# f_-_HomeAutomation.net
KiCad netlist of a schematic drawn in EAGLE
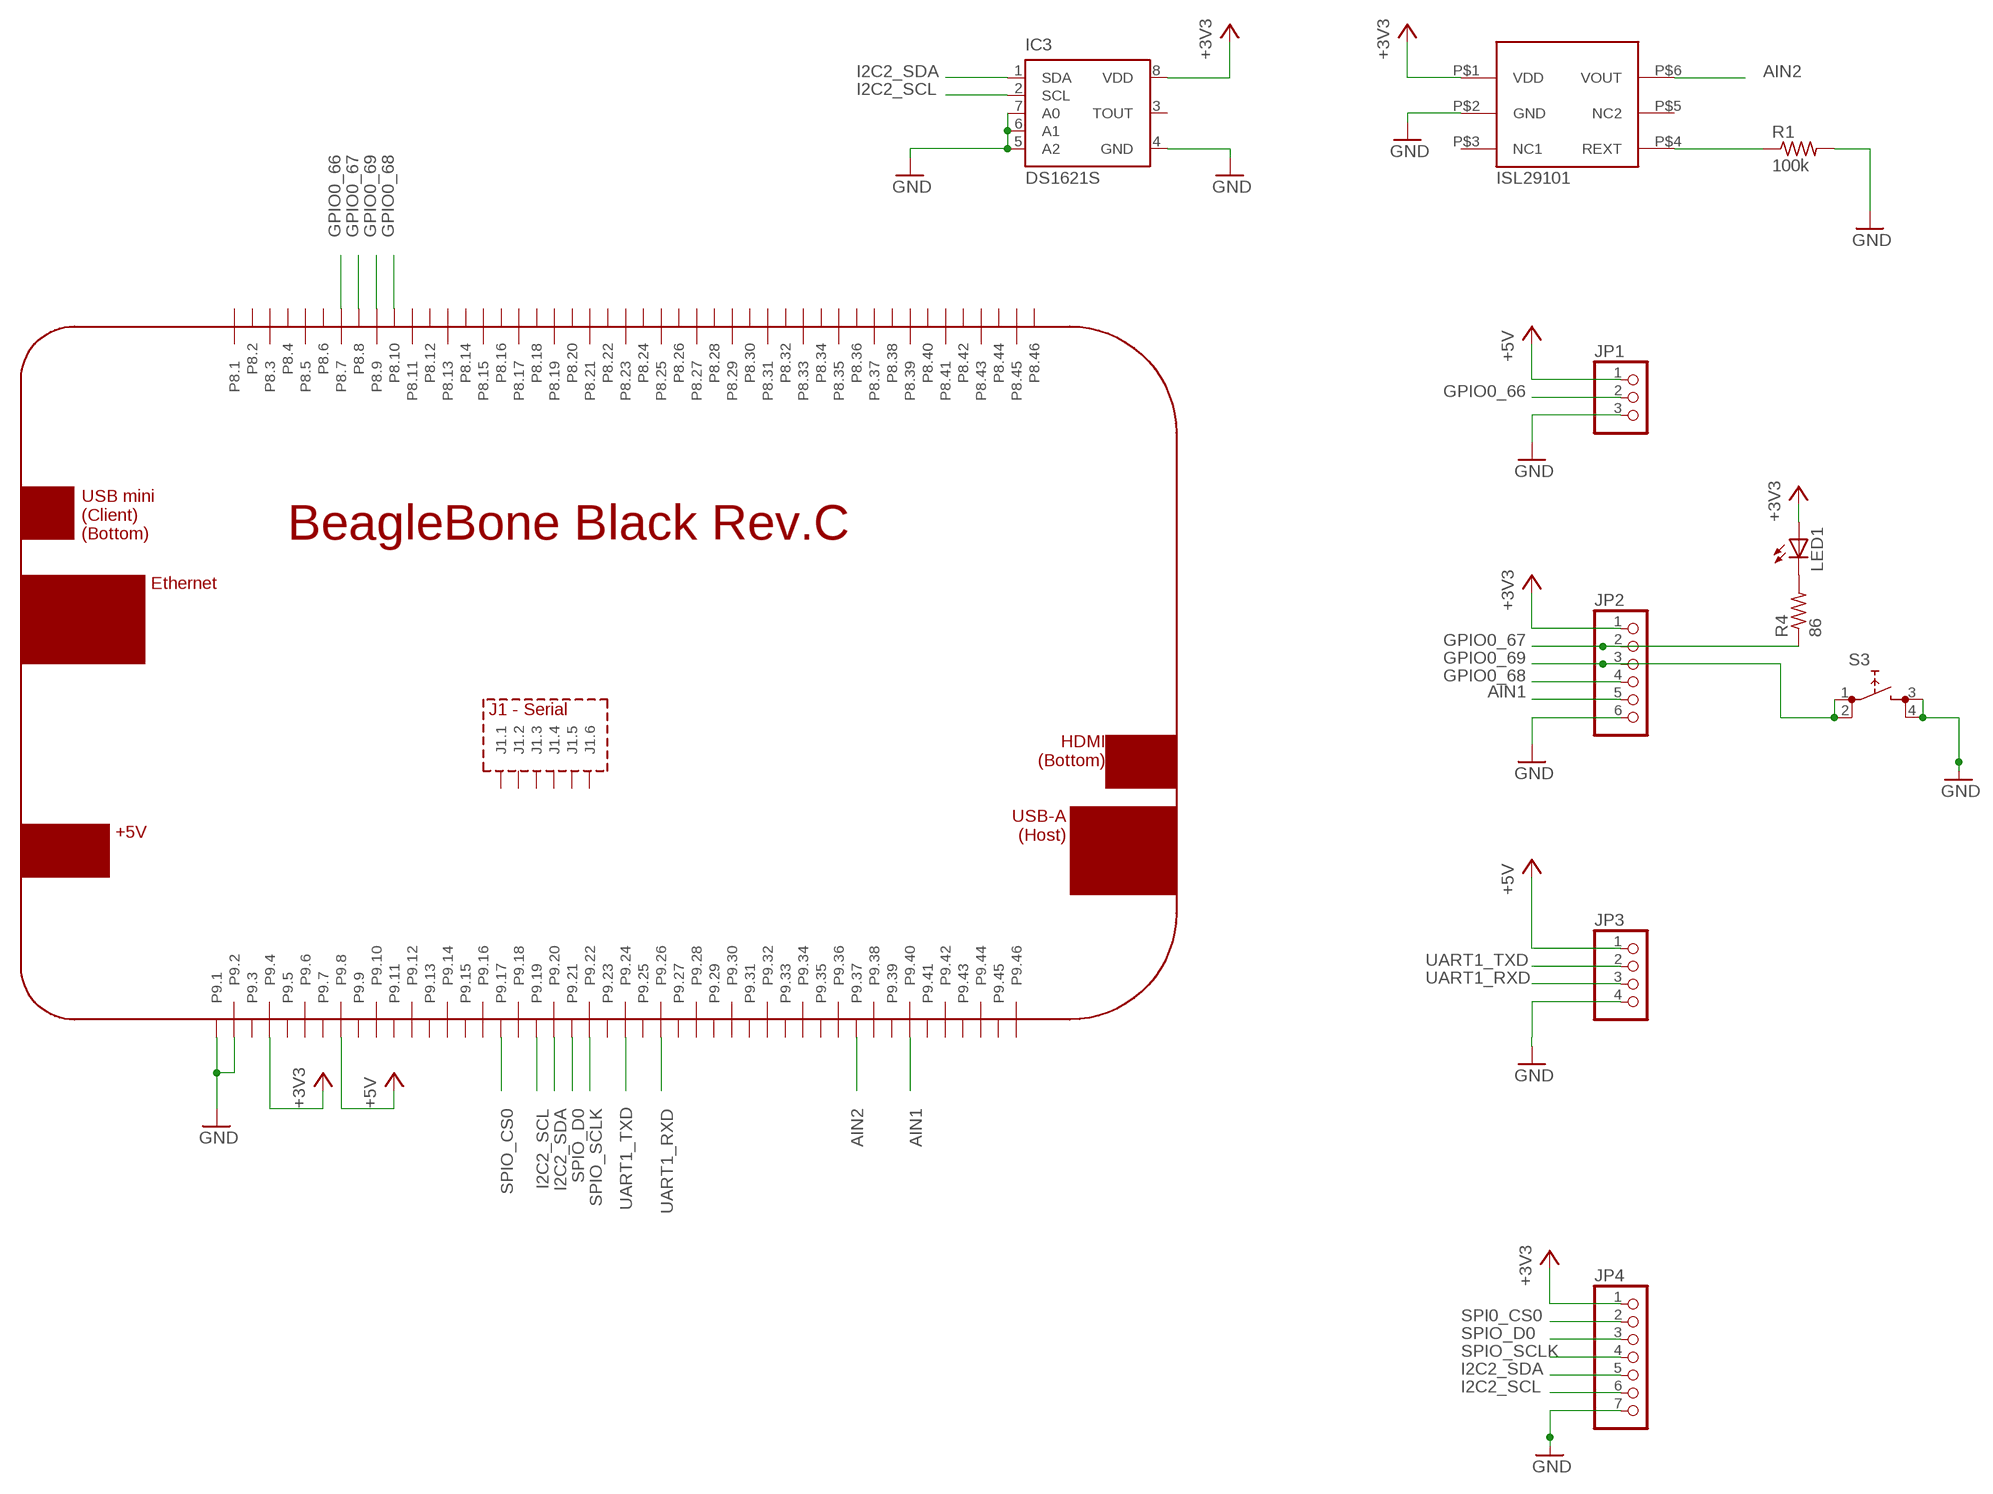
[diagram p0: schematic, sheet 1]

(export (version "E")
  (design (tool "Eeschema 10.0.6"))
  (components
    (comp (ref "IC3")
      (value "DS1621S")
      (footprint "eagle-import:SO08")
      (libsource (lib "eagle-import") (part "DS1621S"))
    )
    (comp (ref "JP1")
      (value "PINHD-1X3")
      (footprint "eagle-import:1X03")
      (libsource (lib "eagle-import") (part "PINHD-1X3"))
    )
    (comp (ref "JP2")
      (value "PINHD-1X6")
      (footprint "eagle-import:1X06")
      (libsource (lib "eagle-import") (part "PINHD-1X6"))
    )
    (comp (ref "JP3")
      (value "PINHD-1X4")
      (footprint "eagle-import:1X04")
      (libsource (lib "eagle-import") (part "PINHD-1X4"))
    )
    (comp (ref "JP4")
      (value "PINHD-1X7")
      (footprint "eagle-import:1X07")
      (libsource (lib "eagle-import") (part "PINHD-1X7"))
    )
    (comp (ref "LED1")
      (value "LED3MM")
      (footprint "eagle-import:LED3MM")
      (libsource (lib "eagle-import") (part "LED3MM"))
    )
    (comp (ref "PCB1")
      (value "BEAGLEBONE_BLACK_CAPE")
      (footprint "eagle-import:BEAGLEBONE_BLACK_CAPE")
      (libsource (lib "eagle-import") (part "BEAGLEBONE_BLACK_CAPE"))
    )
    (comp (ref "R1")
      (value "100k")
      (footprint "eagle-import:R0805")
      (libsource (lib "eagle-import") (part "rcl_334_R-US_R0805"))
    )
    (comp (ref "R4")
      (value "86")
      (footprint "eagle-import:R0805")
      (libsource (lib "eagle-import") (part "R-US_R0805"))
    )
    (comp (ref "S3")
      (value "PUSHBUTTON")
      (footprint "eagle-import:TL1105SP")
      (libsource (lib "eagle-import") (part "PUSHBUTTON"))
    )
    (comp (ref "U$1")
      (value "ISL29101")
      (footprint "eagle-import:ODFN6")
      (libsource (lib "eagle-import") (part "ISL29101"))
    )
  )
  (nets
    (net (code "1") (name "+3V3") (class "Default")
      (node (ref "IC3") (pin "8") (pinfunction "VDD_8") (pintype "power_in"))
      (node (ref "JP2") (pin "1") (pinfunction "1_1") (pintype "passive"))
      (node (ref "JP4") (pin "1") (pinfunction "1_1") (pintype "passive"))
      (node (ref "LED1") (pin "A") (pinfunction "A_A") (pintype "passive"))
      (node (ref "PCB1") (pin "P9.4") (pinfunction "P9.4_P9.4") (pintype "bidirectional"))
      (node (ref "U$1") (pin "P$1") (pinfunction "VDD_P$1") (pintype "bidirectional"))
    )
    (net (code "2") (name "+5V") (class "Default")
      (node (ref "JP1") (pin "1") (pinfunction "1_1") (pintype "passive"))
      (node (ref "JP3") (pin "1") (pinfunction "1_1") (pintype "passive"))
      (node (ref "PCB1") (pin "P9.8") (pinfunction "P9.8_P9.8") (pintype "bidirectional"))
    )
    (net (code "3") (name "/AIN1") (class "Default")
      (node (ref "JP2") (pin "5") (pinfunction "5_5") (pintype "passive"))
      (node (ref "PCB1") (pin "P9.40") (pinfunction "P9.40_P9.40") (pintype "bidirectional"))
    )
    (net (code "4") (name "/AIN2") (class "Default")
      (node (ref "PCB1") (pin "P9.37") (pinfunction "P9.37_P9.37") (pintype "bidirectional"))
      (node (ref "U$1") (pin "P$6") (pinfunction "VOUT_P$6") (pintype "bidirectional"))
    )
    (net (code "5") (name "/GPIO0_66") (class "Default")
      (node (ref "JP1") (pin "2") (pinfunction "2_2") (pintype "passive"))
      (node (ref "PCB1") (pin "P8.7") (pinfunction "P8.7_P8.7") (pintype "bidirectional"))
    )
    (net (code "6") (name "/GPIO0_67") (class "Default")
      (node (ref "JP2") (pin "2") (pinfunction "2_2") (pintype "passive"))
      (node (ref "PCB1") (pin "P8.8") (pinfunction "P8.8_P8.8") (pintype "bidirectional"))
      (node (ref "R4") (pin "1") (pinfunction "1_1") (pintype "passive"))
    )
    (net (code "7") (name "/GPIO0_68") (class "Default")
      (node (ref "JP2") (pin "4") (pinfunction "4_4") (pintype "passive"))
      (node (ref "PCB1") (pin "P8.10") (pinfunction "P8.10_P8.10") (pintype "bidirectional"))
    )
    (net (code "8") (name "/GPIO0_69") (class "Default")
      (node (ref "JP2") (pin "3") (pinfunction "3_3") (pintype "passive"))
      (node (ref "PCB1") (pin "P8.9") (pinfunction "P8.9_P8.9") (pintype "bidirectional"))
      (node (ref "S3") (pin "1") (pinfunction "0_1") (pintype "passive"))
      (node (ref "S3") (pin "2") (pinfunction "0_2") (pintype "passive"))
    )
    (net (code "9") (name "/I2C2_SCL") (class "Default")
      (node (ref "IC3") (pin "2") (pinfunction "SCL_2") (pintype "input"))
      (node (ref "JP4") (pin "6") (pinfunction "6_6") (pintype "passive"))
      (node (ref "PCB1") (pin "P9.19") (pinfunction "P9.19_P9.19") (pintype "bidirectional"))
    )
    (net (code "10") (name "/I2C2_SDA") (class "Default")
      (node (ref "IC3") (pin "1") (pinfunction "SDA_1") (pintype "bidirectional"))
      (node (ref "JP4") (pin "5") (pinfunction "5_5") (pintype "passive"))
      (node (ref "PCB1") (pin "P9.20") (pinfunction "P9.20_P9.20") (pintype "bidirectional"))
    )
    (net (code "11") (name "/SPI0_CS0") (class "Default")
      (node (ref "JP4") (pin "2") (pinfunction "2_2") (pintype "passive"))
    )
    (net (code "12") (name "/SPIO_CS0") (class "Default")
      (node (ref "PCB1") (pin "P9.17") (pinfunction "P9.17_P9.17") (pintype "bidirectional"))
    )
    (net (code "13") (name "/SPIO_D0") (class "Default")
      (node (ref "JP4") (pin "3") (pinfunction "3_3") (pintype "passive"))
      (node (ref "PCB1") (pin "P9.21") (pinfunction "P9.21_P9.21") (pintype "bidirectional"))
    )
    (net (code "14") (name "/SPIO_SCLK") (class "Default")
      (node (ref "JP4") (pin "4") (pinfunction "4_4") (pintype "passive"))
      (node (ref "PCB1") (pin "P9.22") (pinfunction "P9.22_P9.22") (pintype "bidirectional"))
    )
    (net (code "15") (name "/UART1_RXD") (class "Default")
      (node (ref "JP3") (pin "3") (pinfunction "3_3") (pintype "passive"))
      (node (ref "PCB1") (pin "P9.26") (pinfunction "P9.26_P9.26") (pintype "bidirectional"))
    )
    (net (code "16") (name "/UART1_TXD") (class "Default")
      (node (ref "JP3") (pin "2") (pinfunction "2_2") (pintype "passive"))
      (node (ref "PCB1") (pin "P9.24") (pinfunction "P9.24_P9.24") (pintype "bidirectional"))
    )
    (net (code "17") (name "GND") (class "Default")
      (node (ref "IC3") (pin "4") (pinfunction "GND_4") (pintype "power_in"))
      (node (ref "IC3") (pin "5") (pinfunction "A2_5") (pintype "input"))
      (node (ref "IC3") (pin "6") (pinfunction "A1_6") (pintype "input"))
      (node (ref "IC3") (pin "7") (pinfunction "A0_7") (pintype "input"))
      (node (ref "JP1") (pin "3") (pinfunction "3_3") (pintype "passive"))
      (node (ref "JP2") (pin "6") (pinfunction "6_6") (pintype "passive"))
      (node (ref "JP3") (pin "4") (pinfunction "4_4") (pintype "passive"))
      (node (ref "JP4") (pin "7") (pinfunction "7_7") (pintype "passive"))
      (node (ref "PCB1") (pin "P9.1") (pinfunction "P9.1_P9.1") (pintype "bidirectional"))
      (node (ref "PCB1") (pin "P9.2") (pinfunction "P9.2_P9.2") (pintype "bidirectional"))
      (node (ref "R1") (pin "2") (pinfunction "2_2") (pintype "passive"))
      (node (ref "S3") (pin "3") (pinfunction "1_3") (pintype "passive"))
      (node (ref "S3") (pin "4") (pinfunction "1_4") (pintype "passive"))
      (node (ref "U$1") (pin "P$2") (pinfunction "GND_P$2") (pintype "bidirectional"))
    )
    (net (code "18") (name "Net-(LED1-C)") (class "Default")
      (node (ref "LED1") (pin "K") (pinfunction "C_K") (pintype "passive"))
      (node (ref "R4") (pin "2") (pinfunction "2_2") (pintype "passive"))
    )
    (net (code "19") (name "Net-(U$1-REXT)") (class "Default")
      (node (ref "R1") (pin "1") (pinfunction "1_1") (pintype "passive"))
      (node (ref "U$1") (pin "P$4") (pinfunction "REXT_P$4") (pintype "bidirectional"))
    )
    (net (code "20") (name "unconnected-(IC3-TOUT-Pad3)") (class "Default")
      (node (ref "IC3") (pin "3") (pinfunction "TOUT_3") (pintype "output"))
    )
    (net (code "21") (name "unconnected-(PCB1-PadJ1.1)") (class "Default")
      (node (ref "PCB1") (pin "J1.1") (pinfunction "J1.1_J1.1") (pintype "bidirectional"))
    )
    (net (code "22") (name "unconnected-(PCB1-PadJ1.2)") (class "Default")
      (node (ref "PCB1") (pin "J1.2") (pinfunction "J1.2_J1.2") (pintype "bidirectional"))
    )
    (net (code "23") (name "unconnected-(PCB1-PadJ1.3)") (class "Default")
      (node (ref "PCB1") (pin "J1.3") (pinfunction "J1.3_J1.3") (pintype "bidirectional"))
    )
    (net (code "24") (name "unconnected-(PCB1-PadJ1.4)") (class "Default")
      (node (ref "PCB1") (pin "J1.4") (pinfunction "J1.4_J1.4") (pintype "bidirectional"))
    )
    (net (code "25") (name "unconnected-(PCB1-PadJ1.5)") (class "Default")
      (node (ref "PCB1") (pin "J1.5") (pinfunction "J1.5_J1.5") (pintype "bidirectional"))
    )
    (net (code "26") (name "unconnected-(PCB1-PadJ1.6)") (class "Default")
      (node (ref "PCB1") (pin "J1.6") (pinfunction "J1.6_J1.6") (pintype "bidirectional"))
    )
    (net (code "27") (name "unconnected-(PCB1-PadP8.1)") (class "Default")
      (node (ref "PCB1") (pin "P8.1") (pinfunction "P8.1_P8.1") (pintype "bidirectional"))
    )
    (net (code "28") (name "unconnected-(PCB1-PadP8.2)") (class "Default")
      (node (ref "PCB1") (pin "P8.2") (pinfunction "P8.2_P8.2") (pintype "bidirectional"))
    )
    (net (code "29") (name "unconnected-(PCB1-PadP8.3)") (class "Default")
      (node (ref "PCB1") (pin "P8.3") (pinfunction "P8.3_P8.3") (pintype "bidirectional"))
    )
    (net (code "30") (name "unconnected-(PCB1-PadP8.4)") (class "Default")
      (node (ref "PCB1") (pin "P8.4") (pinfunction "P8.4_P8.4") (pintype "bidirectional"))
    )
    (net (code "31") (name "unconnected-(PCB1-PadP8.5)") (class "Default")
      (node (ref "PCB1") (pin "P8.5") (pinfunction "P8.5_P8.5") (pintype "bidirectional"))
    )
    (net (code "32") (name "unconnected-(PCB1-PadP8.6)") (class "Default")
      (node (ref "PCB1") (pin "P8.6") (pinfunction "P8.6_P8.6") (pintype "bidirectional"))
    )
    (net (code "33") (name "unconnected-(PCB1-PadP8.11)") (class "Default")
      (node (ref "PCB1") (pin "P8.11") (pinfunction "P8.11_P8.11") (pintype "bidirectional"))
    )
    (net (code "34") (name "unconnected-(PCB1-PadP8.12)") (class "Default")
      (node (ref "PCB1") (pin "P8.12") (pinfunction "P8.12_P8.12") (pintype "bidirectional"))
    )
    (net (code "35") (name "unconnected-(PCB1-PadP8.13)") (class "Default")
      (node (ref "PCB1") (pin "P8.13") (pinfunction "P8.13_P8.13") (pintype "bidirectional"))
    )
    (net (code "36") (name "unconnected-(PCB1-PadP8.14)") (class "Default")
      (node (ref "PCB1") (pin "P8.14") (pinfunction "P8.14_P8.14") (pintype "bidirectional"))
    )
    (net (code "37") (name "unconnected-(PCB1-PadP8.15)") (class "Default")
      (node (ref "PCB1") (pin "P8.15") (pinfunction "P8.15_P8.15") (pintype "bidirectional"))
    )
    (net (code "38") (name "unconnected-(PCB1-PadP8.16)") (class "Default")
      (node (ref "PCB1") (pin "P8.16") (pinfunction "P8.16_P8.16") (pintype "bidirectional"))
    )
    (net (code "39") (name "unconnected-(PCB1-PadP8.17)") (class "Default")
      (node (ref "PCB1") (pin "P8.17") (pinfunction "P8.17_P8.17") (pintype "bidirectional"))
    )
    (net (code "40") (name "unconnected-(PCB1-PadP8.18)") (class "Default")
      (node (ref "PCB1") (pin "P8.18") (pinfunction "P8.18_P8.18") (pintype "bidirectional"))
    )
    (net (code "41") (name "unconnected-(PCB1-PadP8.19)") (class "Default")
      (node (ref "PCB1") (pin "P8.19") (pinfunction "P8.19_P8.19") (pintype "bidirectional"))
    )
    (net (code "42") (name "unconnected-(PCB1-PadP8.20)") (class "Default")
      (node (ref "PCB1") (pin "P8.20") (pinfunction "P8.20_P8.20") (pintype "bidirectional"))
    )
    (net (code "43") (name "unconnected-(PCB1-PadP8.21)") (class "Default")
      (node (ref "PCB1") (pin "P8.21") (pinfunction "P8.21_P8.21") (pintype "bidirectional"))
    )
    (net (code "44") (name "unconnected-(PCB1-PadP8.22)") (class "Default")
      (node (ref "PCB1") (pin "P8.22") (pinfunction "P8.22_P8.22") (pintype "bidirectional"))
    )
    (net (code "45") (name "unconnected-(PCB1-PadP8.23)") (class "Default")
      (node (ref "PCB1") (pin "P8.23") (pinfunction "P8.23_P8.23") (pintype "bidirectional"))
    )
    (net (code "46") (name "unconnected-(PCB1-PadP8.24)") (class "Default")
      (node (ref "PCB1") (pin "P8.24") (pinfunction "P8.24_P8.24") (pintype "bidirectional"))
    )
    (net (code "47") (name "unconnected-(PCB1-PadP8.25)") (class "Default")
      (node (ref "PCB1") (pin "P8.25") (pinfunction "P8.25_P8.25") (pintype "bidirectional"))
    )
    (net (code "48") (name "unconnected-(PCB1-PadP8.26)") (class "Default")
      (node (ref "PCB1") (pin "P8.26") (pinfunction "P8.26_P8.26") (pintype "bidirectional"))
    )
    (net (code "49") (name "unconnected-(PCB1-PadP8.27)") (class "Default")
      (node (ref "PCB1") (pin "P8.27") (pinfunction "P8.27_P8.27") (pintype "bidirectional"))
    )
    (net (code "50") (name "unconnected-(PCB1-PadP8.28)") (class "Default")
      (node (ref "PCB1") (pin "P8.28") (pinfunction "P8.28_P8.28") (pintype "bidirectional"))
    )
    (net (code "51") (name "unconnected-(PCB1-PadP8.29)") (class "Default")
      (node (ref "PCB1") (pin "P8.29") (pinfunction "P8.29_P8.29") (pintype "bidirectional"))
    )
    (net (code "52") (name "unconnected-(PCB1-PadP8.30)") (class "Default")
      (node (ref "PCB1") (pin "P8.30") (pinfunction "P8.30_P8.30") (pintype "bidirectional"))
    )
    (net (code "53") (name "unconnected-(PCB1-PadP8.31)") (class "Default")
      (node (ref "PCB1") (pin "P8.31") (pinfunction "P8.31_P8.31") (pintype "bidirectional"))
    )
    (net (code "54") (name "unconnected-(PCB1-PadP8.32)") (class "Default")
      (node (ref "PCB1") (pin "P8.32") (pinfunction "P8.32_P8.32") (pintype "bidirectional"))
    )
    (net (code "55") (name "unconnected-(PCB1-PadP8.33)") (class "Default")
      (node (ref "PCB1") (pin "P8.33") (pinfunction "P8.33_P8.33") (pintype "bidirectional"))
    )
    (net (code "56") (name "unconnected-(PCB1-PadP8.34)") (class "Default")
      (node (ref "PCB1") (pin "P8.34") (pinfunction "P8.34_P8.34") (pintype "bidirectional"))
    )
    (net (code "57") (name "unconnected-(PCB1-PadP8.35)") (class "Default")
      (node (ref "PCB1") (pin "P8.35") (pinfunction "P8.35_P8.35") (pintype "bidirectional"))
    )
    (net (code "58") (name "unconnected-(PCB1-PadP8.36)") (class "Default")
      (node (ref "PCB1") (pin "P8.36") (pinfunction "P8.36_P8.36") (pintype "bidirectional"))
    )
    (net (code "59") (name "unconnected-(PCB1-PadP8.37)") (class "Default")
      (node (ref "PCB1") (pin "P8.37") (pinfunction "P8.37_P8.37") (pintype "bidirectional"))
    )
    (net (code "60") (name "unconnected-(PCB1-PadP8.38)") (class "Default")
      (node (ref "PCB1") (pin "P8.38") (pinfunction "P8.38_P8.38") (pintype "bidirectional"))
    )
    (net (code "61") (name "unconnected-(PCB1-PadP8.39)") (class "Default")
      (node (ref "PCB1") (pin "P8.39") (pinfunction "P8.39_P8.39") (pintype "bidirectional"))
    )
    (net (code "62") (name "unconnected-(PCB1-PadP8.40)") (class "Default")
      (node (ref "PCB1") (pin "P8.40") (pinfunction "P8.40_P8.40") (pintype "bidirectional"))
    )
    (net (code "63") (name "unconnected-(PCB1-PadP8.41)") (class "Default")
      (node (ref "PCB1") (pin "P8.41") (pinfunction "P8.41_P8.41") (pintype "bidirectional"))
    )
    (net (code "64") (name "unconnected-(PCB1-PadP8.42)") (class "Default")
      (node (ref "PCB1") (pin "P8.42") (pinfunction "P8.42_P8.42") (pintype "bidirectional"))
    )
    (net (code "65") (name "unconnected-(PCB1-PadP8.43)") (class "Default")
      (node (ref "PCB1") (pin "P8.43") (pinfunction "P8.43_P8.43") (pintype "bidirectional"))
    )
    (net (code "66") (name "unconnected-(PCB1-PadP8.44)") (class "Default")
      (node (ref "PCB1") (pin "P8.44") (pinfunction "P8.44_P8.44") (pintype "bidirectional"))
    )
    (net (code "67") (name "unconnected-(PCB1-PadP8.45)") (class "Default")
      (node (ref "PCB1") (pin "P8.45") (pinfunction "P8.45_P8.45") (pintype "bidirectional"))
    )
    (net (code "68") (name "unconnected-(PCB1-PadP8.46)") (class "Default")
      (node (ref "PCB1") (pin "P8.46") (pinfunction "P8.46_P8.46") (pintype "bidirectional"))
    )
    (net (code "69") (name "unconnected-(PCB1-PadP9.3)") (class "Default")
      (node (ref "PCB1") (pin "P9.3") (pinfunction "P9.3_P9.3") (pintype "bidirectional"))
    )
    (net (code "70") (name "unconnected-(PCB1-PadP9.5)") (class "Default")
      (node (ref "PCB1") (pin "P9.5") (pinfunction "P9.5_P9.5") (pintype "bidirectional"))
    )
    (net (code "71") (name "unconnected-(PCB1-PadP9.6)") (class "Default")
      (node (ref "PCB1") (pin "P9.6") (pinfunction "P9.6_P9.6") (pintype "bidirectional"))
    )
    (net (code "72") (name "unconnected-(PCB1-PadP9.7)") (class "Default")
      (node (ref "PCB1") (pin "P9.7") (pinfunction "P9.7_P9.7") (pintype "bidirectional"))
    )
    (net (code "73") (name "unconnected-(PCB1-PadP9.9)") (class "Default")
      (node (ref "PCB1") (pin "P9.9") (pinfunction "P9.9_P9.9") (pintype "bidirectional"))
    )
    (net (code "74") (name "unconnected-(PCB1-PadP9.10)") (class "Default")
      (node (ref "PCB1") (pin "P9.10") (pinfunction "P9.10_P9.10") (pintype "bidirectional"))
    )
    (net (code "75") (name "unconnected-(PCB1-PadP9.11)") (class "Default")
      (node (ref "PCB1") (pin "P9.11") (pinfunction "P9.11_P9.11") (pintype "bidirectional"))
    )
    (net (code "76") (name "unconnected-(PCB1-PadP9.12)") (class "Default")
      (node (ref "PCB1") (pin "P9.12") (pinfunction "P9.12_P9.12") (pintype "bidirectional"))
    )
    (net (code "77") (name "unconnected-(PCB1-PadP9.13)") (class "Default")
      (node (ref "PCB1") (pin "P9.13") (pinfunction "P9.13_P9.13") (pintype "bidirectional"))
    )
    (net (code "78") (name "unconnected-(PCB1-PadP9.14)") (class "Default")
      (node (ref "PCB1") (pin "P9.14") (pinfunction "P9.14_P9.14") (pintype "bidirectional"))
    )
    (net (code "79") (name "unconnected-(PCB1-PadP9.15)") (class "Default")
      (node (ref "PCB1") (pin "P9.15") (pinfunction "P9.15_P9.15") (pintype "bidirectional"))
    )
    (net (code "80") (name "unconnected-(PCB1-PadP9.16)") (class "Default")
      (node (ref "PCB1") (pin "P9.16") (pinfunction "P9.16_P9.16") (pintype "bidirectional"))
    )
    (net (code "81") (name "unconnected-(PCB1-PadP9.18)") (class "Default")
      (node (ref "PCB1") (pin "P9.18") (pinfunction "P9.18_P9.18") (pintype "bidirectional"))
    )
    (net (code "82") (name "unconnected-(PCB1-PadP9.23)") (class "Default")
      (node (ref "PCB1") (pin "P9.23") (pinfunction "P9.23_P9.23") (pintype "bidirectional"))
    )
    (net (code "83") (name "unconnected-(PCB1-PadP9.25)") (class "Default")
      (node (ref "PCB1") (pin "P9.25") (pinfunction "P9.25_P9.25") (pintype "bidirectional"))
    )
    (net (code "84") (name "unconnected-(PCB1-PadP9.27)") (class "Default")
      (node (ref "PCB1") (pin "P9.27") (pinfunction "P9.27_P9.27") (pintype "bidirectional"))
    )
    (net (code "85") (name "unconnected-(PCB1-PadP9.28)") (class "Default")
      (node (ref "PCB1") (pin "P9.28") (pinfunction "P9.28_P9.28") (pintype "bidirectional"))
    )
    (net (code "86") (name "unconnected-(PCB1-PadP9.29)") (class "Default")
      (node (ref "PCB1") (pin "P9.29") (pinfunction "P9.29_P9.29") (pintype "bidirectional"))
    )
    (net (code "87") (name "unconnected-(PCB1-PadP9.30)") (class "Default")
      (node (ref "PCB1") (pin "P9.30") (pinfunction "P9.30_P9.30") (pintype "bidirectional"))
    )
    (net (code "88") (name "unconnected-(PCB1-PadP9.31)") (class "Default")
      (node (ref "PCB1") (pin "P9.31") (pinfunction "P9.31_P9.31") (pintype "bidirectional"))
    )
    (net (code "89") (name "unconnected-(PCB1-PadP9.32)") (class "Default")
      (node (ref "PCB1") (pin "P9.32") (pinfunction "P9.32_P9.32") (pintype "bidirectional"))
    )
    (net (code "90") (name "unconnected-(PCB1-PadP9.33)") (class "Default")
      (node (ref "PCB1") (pin "P9.33") (pinfunction "P9.33_P9.33") (pintype "bidirectional"))
    )
    (net (code "91") (name "unconnected-(PCB1-PadP9.34)") (class "Default")
      (node (ref "PCB1") (pin "P9.34") (pinfunction "P9.34_P9.34") (pintype "bidirectional"))
    )
    (net (code "92") (name "unconnected-(PCB1-PadP9.35)") (class "Default")
      (node (ref "PCB1") (pin "P9.35") (pinfunction "P9.35_P9.35") (pintype "bidirectional"))
    )
    (net (code "93") (name "unconnected-(PCB1-PadP9.36)") (class "Default")
      (node (ref "PCB1") (pin "P9.36") (pinfunction "P9.36_P9.36") (pintype "bidirectional"))
    )
    (net (code "94") (name "unconnected-(PCB1-PadP9.38)") (class "Default")
      (node (ref "PCB1") (pin "P9.38") (pinfunction "P9.38_P9.38") (pintype "bidirectional"))
    )
    (net (code "95") (name "unconnected-(PCB1-PadP9.39)") (class "Default")
      (node (ref "PCB1") (pin "P9.39") (pinfunction "P9.39_P9.39") (pintype "bidirectional"))
    )
    (net (code "96") (name "unconnected-(PCB1-PadP9.41)") (class "Default")
      (node (ref "PCB1") (pin "P9.41") (pinfunction "P9.41_P9.41") (pintype "bidirectional"))
    )
    (net (code "97") (name "unconnected-(PCB1-PadP9.42)") (class "Default")
      (node (ref "PCB1") (pin "P9.42") (pinfunction "P9.42_P9.42") (pintype "bidirectional"))
    )
    (net (code "98") (name "unconnected-(PCB1-PadP9.43)") (class "Default")
      (node (ref "PCB1") (pin "P9.43") (pinfunction "P9.43_P9.43") (pintype "bidirectional"))
    )
    (net (code "99") (name "unconnected-(PCB1-PadP9.44)") (class "Default")
      (node (ref "PCB1") (pin "P9.44") (pinfunction "P9.44_P9.44") (pintype "bidirectional"))
    )
    (net (code "100") (name "unconnected-(PCB1-PadP9.45)") (class "Default")
      (node (ref "PCB1") (pin "P9.45") (pinfunction "P9.45_P9.45") (pintype "bidirectional"))
    )
    (net (code "101") (name "unconnected-(PCB1-PadP9.46)") (class "Default")
      (node (ref "PCB1") (pin "P9.46") (pinfunction "P9.46_P9.46") (pintype "bidirectional"))
    )
    (net (code "102") (name "unconnected-(U$1-NC1-PadP$3)") (class "Default")
      (node (ref "U$1") (pin "P$3") (pinfunction "NC1_P$3") (pintype "bidirectional"))
    )
    (net (code "103") (name "unconnected-(U$1-NC2-PadP$5)") (class "Default")
      (node (ref "U$1") (pin "P$5") (pinfunction "NC2_P$5") (pintype "bidirectional"))
    )
  )
)
